# USB_OTG_FS.net
KiCad netlist of a schematic drawn in Altium Designer
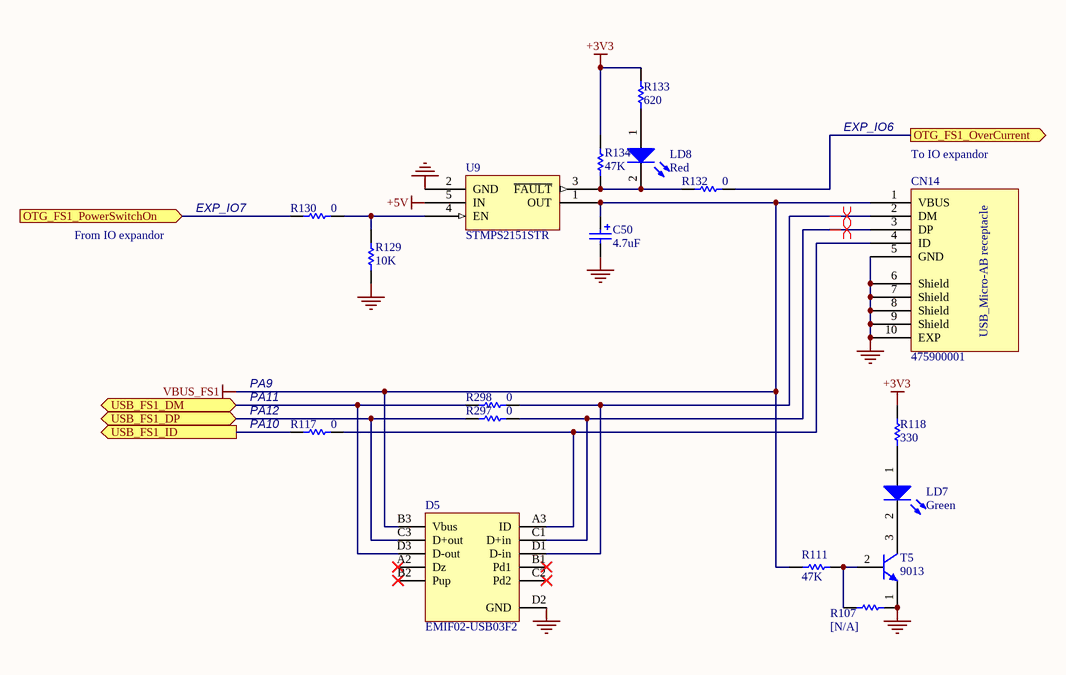
[diagram p0: USB_OTG_FS.SchDoc]

(export (version "E")
  (design (tool "Eeschema 10.0.6"))
  (components
    (comp (ref "C50")
      (value "4.7uF")
      (footprint "TAN-A")
      (description "Polarized Capacitor (Radial)")
      (fields (field (name "PUBLISHER") "Altium Limited"))
      (libsource (lib "Miscellaneous Devices") (part "Cap Pol1"))
    )
    (comp (ref "CN14")
      (value "475900001")
      (footprint "MOLEX_47590001")
      (libsource (lib "mb1045") (part "475900001"))
    )
    (comp (ref "D5")
      (value "EMIF02-USB03F2")
      (footprint "BGA11_0R5_1R57X2R07")
      (libsource (lib "mb1045") (part "EMIF02-USB03F2"))
    )
    (comp (ref "LD7")
      (value "Green")
      (footprint "0603D")
      (description "Typical RED, GREEN, YELLOW, AMBER GaAs LED")
      (fields (field (name "PUBLISHER") "Altium Limited"))
      (libsource (lib "Miscellaneous Devices") (part "LED2"))
    )
    (comp (ref "LD8")
      (value "Red")
      (footprint "0603D")
      (description "Typical RED, GREEN, YELLOW, AMBER GaAs LED")
      (fields (field (name "PUBLISHER") "Altium Limited"))
      (libsource (lib "Miscellaneous Devices") (part "LED2"))
    )
    (comp (ref "R107")
      (value "[N/A]")
      (footprint "0603R")
      (description "Resistor")
      (fields (field (name "PUBLISHER") "Altium Limited"))
      (libsource (lib "Miscellaneous Devices") (part "res1"))
    )
    (comp (ref "R111")
      (value "47K")
      (footprint "0603R")
      (description "Resistor")
      (fields (field (name "PUBLISHER") "Altium Limited"))
      (libsource (lib "Miscellaneous Devices") (part "res1"))
    )
    (comp (ref "R117")
      (value "0")
      (footprint "0603R")
      (description "Resistor")
      (fields (field (name "PUBLISHER") "Altium Limited"))
      (libsource (lib "Miscellaneous Devices") (part "Res1"))
    )
    (comp (ref "R118")
      (value "330")
      (footprint "0603R")
      (description "Resistor")
      (fields (field (name "PUBLISHER") "Altium Limited"))
      (libsource (lib "Miscellaneous Devices") (part "res1"))
    )
    (comp (ref "R129")
      (value "10K")
      (footprint "0603R")
      (description "Resistor")
      (fields (field (name "PUBLISHER") "Altium Limited"))
      (libsource (lib "Miscellaneous Devices") (part "Res1"))
    )
    (comp (ref "R130")
      (value "0")
      (footprint "0603R")
      (description "Resistor")
      (fields (field (name "PUBLISHER") "Altium Limited"))
      (libsource (lib "Miscellaneous Devices") (part "Res1"))
    )
    (comp (ref "R132")
      (value "0")
      (footprint "0603R")
      (description "Resistor")
      (fields (field (name "PUBLISHER") "Altium Limited"))
      (libsource (lib "Miscellaneous Devices") (part "Res1"))
    )
    (comp (ref "R133")
      (value "620")
      (footprint "0603R")
      (description "Resistor")
      (fields (field (name "PUBLISHER") "Altium Limited"))
      (libsource (lib "Miscellaneous Devices") (part "Res1"))
    )
    (comp (ref "R134")
      (value "47K")
      (footprint "0603R")
      (description "Resistor")
      (fields (field (name "PUBLISHER") "Altium Limited"))
      (libsource (lib "Miscellaneous Devices") (part "res1"))
    )
    (comp (ref "R297")
      (value "0")
      (footprint "0603R")
      (description "Resistor")
      (fields (field (name "PUBLISHER") "Altium Limited"))
      (libsource (lib "Miscellaneous Devices") (part "Res1"))
    )
    (comp (ref "R298")
      (value "0")
      (footprint "0603R")
      (description "Resistor")
      (fields (field (name "PUBLISHER") "Altium Limited"))
      (libsource (lib "Miscellaneous Devices") (part "Res1"))
    )
    (comp (ref "T5")
      (value "9013")
      (footprint "SOT23-213")
      (description "NPN Bipolar Transistor")
      (fields (field (name "PUBLISHER") "Altium Limited"))
      (libsource (lib "mb1045") (part "NPN"))
    )
    (comp (ref "U9")
      (value "STMPS2151STR")
      (footprint "SOT23-5")
      (libsource (lib "mb1045") (part "STMPS2141STR"))
    )
  )
  (nets
    (net (code "1") (name "+3V3") (class "Default")
      (node (ref "R118") (pin "2") (pinfunction "2_2") (pintype "passive"))
      (node (ref "R133") (pin "2") (pinfunction "2_2") (pintype "passive"))
      (node (ref "R134") (pin "1") (pinfunction "1_1") (pintype "passive"))
    )
    (net (code "2") (name "+5V") (class "Default")
      (node (ref "U9") (pin "5") (pinfunction "IN_5") (pintype "passive"))
    )
    (net (code "3") (name "/OTG_FS1_OverCurrent") (class "Default")
      (node (ref "R132") (pin "1") (pinfunction "1_1") (pintype "passive"))
    )
    (net (code "4") (name "/OTG_FS1_PowerSwitchOn") (class "Default")
      (node (ref "R130") (pin "2") (pinfunction "2_2") (pintype "passive"))
    )
    (net (code "5") (name "/USB_FS1_DM") (class "Default")
      (node (ref "D5") (pin "D3") (pinfunction "D-out_D3") (pintype "passive"))
      (node (ref "R298") (pin "2") (pinfunction "2_2") (pintype "passive"))
    )
    (net (code "6") (name "/USB_FS1_DP") (class "Default")
      (node (ref "D5") (pin "C3") (pinfunction "D+out_C3") (pintype "passive"))
      (node (ref "R297") (pin "2") (pinfunction "2_2") (pintype "passive"))
    )
    (net (code "7") (name "/USB_FS1_ID") (class "Default")
      (node (ref "R117") (pin "2") (pinfunction "2_2") (pintype "passive"))
    )
    (net (code "8") (name "GND") (class "Default")
      (node (ref "C50") (pin "2") (pinfunction "2_2") (pintype "passive"))
      (node (ref "CN14") (pin "10") (pinfunction "EXP_10") (pintype "passive"))
      (node (ref "CN14") (pin "5") (pinfunction "GND_5") (pintype "passive"))
      (node (ref "CN14") (pin "6") (pinfunction "Shield_6") (pintype "passive"))
      (node (ref "CN14") (pin "7") (pinfunction "Shield_7") (pintype "passive"))
      (node (ref "CN14") (pin "8") (pinfunction "Shield_8") (pintype "passive"))
      (node (ref "CN14") (pin "9") (pinfunction "Shield_9") (pintype "passive"))
      (node (ref "D5") (pin "D2") (pinfunction "GND_D2") (pintype "passive"))
      (node (ref "R107") (pin "1") (pinfunction "1_1") (pintype "passive"))
      (node (ref "R129") (pin "1") (pinfunction "1_1") (pintype "passive"))
      (node (ref "T5") (pin "1") (pinfunction "E_1") (pintype "passive"))
      (node (ref "U9") (pin "2") (pinfunction "GND_2") (pintype "passive"))
    )
    (net (code "9") (name "Net-(CN14-DM)") (class "Default")
      (node (ref "CN14") (pin "2") (pinfunction "DM_2") (pintype "passive"))
      (node (ref "D5") (pin "D1") (pinfunction "D-in_D1") (pintype "passive"))
      (node (ref "R298") (pin "1") (pinfunction "1_1") (pintype "passive"))
    )
    (net (code "10") (name "Net-(CN14-DP)") (class "Default")
      (node (ref "CN14") (pin "3") (pinfunction "DP_3") (pintype "passive"))
      (node (ref "D5") (pin "C1") (pinfunction "D+in_C1") (pintype "passive"))
      (node (ref "R297") (pin "1") (pinfunction "1_1") (pintype "passive"))
    )
    (net (code "11") (name "Net-(CN14-ID)") (class "Default")
      (node (ref "CN14") (pin "4") (pinfunction "ID_4") (pintype "passive"))
      (node (ref "D5") (pin "A3") (pinfunction "ID_A3") (pintype "passive"))
      (node (ref "R117") (pin "1") (pinfunction "1_1") (pintype "passive"))
    )
    (net (code "12") (name "Net-(LD7-A)") (class "Default")
      (node (ref "LD7") (pin "1") (pinfunction "A_1") (pintype "passive"))
      (node (ref "R118") (pin "1") (pinfunction "1_1") (pintype "passive"))
    )
    (net (code "13") (name "Net-(LD7-K)") (class "Default")
      (node (ref "LD7") (pin "2") (pinfunction "K_2") (pintype "passive"))
      (node (ref "T5") (pin "3") (pinfunction "C_3") (pintype "passive"))
    )
    (net (code "14") (name "Net-(LD8-A)") (class "Default")
      (node (ref "LD8") (pin "1") (pinfunction "A_1") (pintype "passive"))
      (node (ref "R133") (pin "1") (pinfunction "1_1") (pintype "passive"))
    )
    (net (code "15") (name "Net-(LD8-K)") (class "Default")
      (node (ref "LD8") (pin "2") (pinfunction "K_2") (pintype "passive"))
      (node (ref "R132") (pin "2") (pinfunction "2_2") (pintype "passive"))
      (node (ref "R134") (pin "2") (pinfunction "2_2") (pintype "passive"))
      (node (ref "U9") (pin "3") (pinfunction "~{FAULT}_3") (pintype "output"))
    )
    (net (code "16") (name "Net-(T5-B)") (class "Default")
      (node (ref "R107") (pin "2") (pinfunction "2_2") (pintype "passive"))
      (node (ref "R111") (pin "2") (pinfunction "2_2") (pintype "passive"))
      (node (ref "T5") (pin "2") (pinfunction "B_2") (pintype "passive"))
    )
    (net (code "17") (name "Net-(U9-EN)") (class "Default")
      (node (ref "R129") (pin "2") (pinfunction "2_2") (pintype "passive"))
      (node (ref "R130") (pin "1") (pinfunction "1_1") (pintype "passive"))
      (node (ref "U9") (pin "4") (pinfunction "EN_4") (pintype "input"))
    )
    (net (code "18") (name "VBUS_FS1") (class "Default")
      (node (ref "C50") (pin "1") (pinfunction "1_1") (pintype "passive"))
      (node (ref "CN14") (pin "1") (pinfunction "VBUS_1") (pintype "passive"))
      (node (ref "D5") (pin "B3") (pinfunction "Vbus_B3") (pintype "passive"))
      (node (ref "R111") (pin "1") (pinfunction "1_1") (pintype "passive"))
      (node (ref "U9") (pin "1") (pinfunction "OUT_1") (pintype "passive"))
    )
    (net (code "19") (name "unconnected-(D5-Dz-PadA2)") (class "Default")
      (node (ref "D5") (pin "A2") (pinfunction "Dz_A2") (pintype "passive+no_connect"))
    )
    (net (code "20") (name "unconnected-(D5-Pd1-PadB1)") (class "Default")
      (node (ref "D5") (pin "B1") (pinfunction "Pd1_B1") (pintype "passive+no_connect"))
    )
    (net (code "21") (name "unconnected-(D5-Pd2-PadC2)") (class "Default")
      (node (ref "D5") (pin "C2") (pinfunction "Pd2_C2") (pintype "passive+no_connect"))
    )
    (net (code "22") (name "unconnected-(D5-Pup-PadB2)") (class "Default")
      (node (ref "D5") (pin "B2") (pinfunction "Pup_B2") (pintype "passive+no_connect"))
    )
  )
)
